# 07_MSM8916_GPIO.net
KiCad netlist of a schematic drawn in Altium Designer
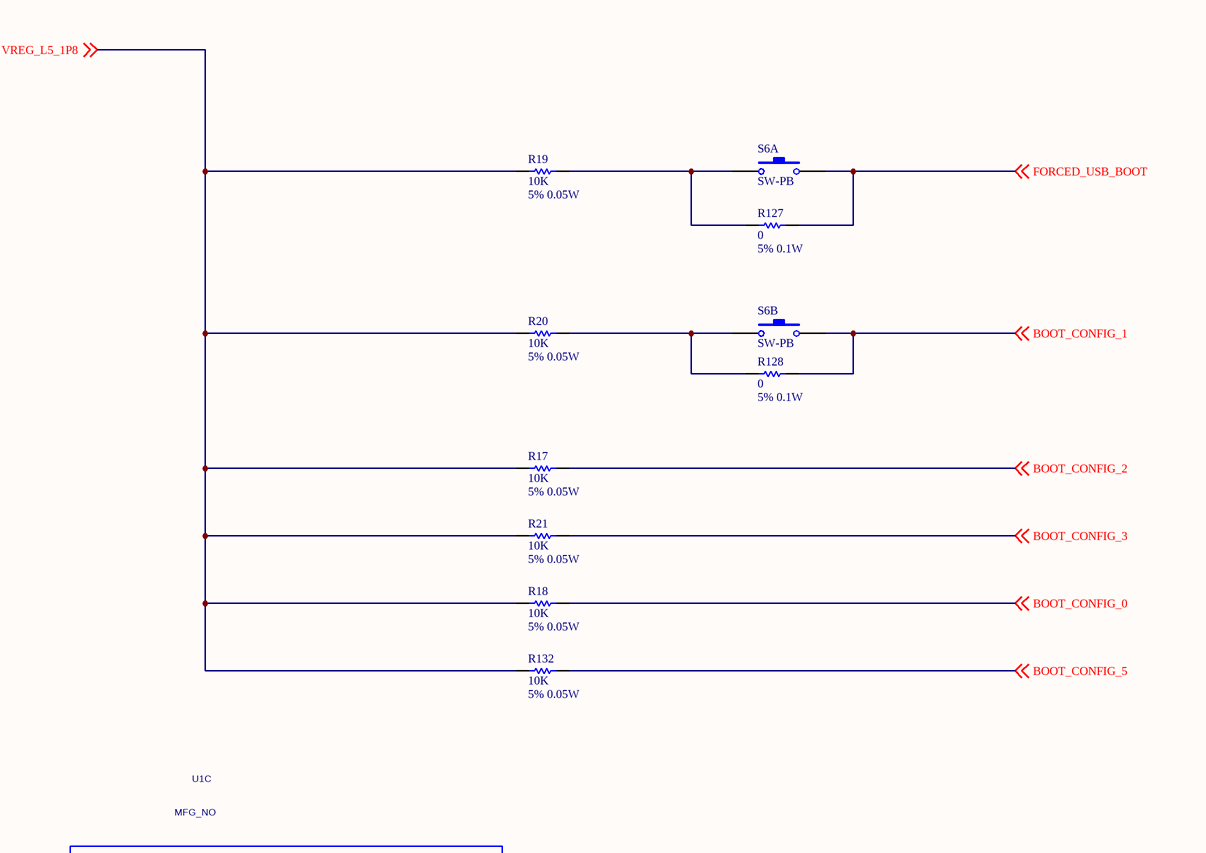
[diagram p0: 07_MSM8916_GPIO.SchDoc, top left]
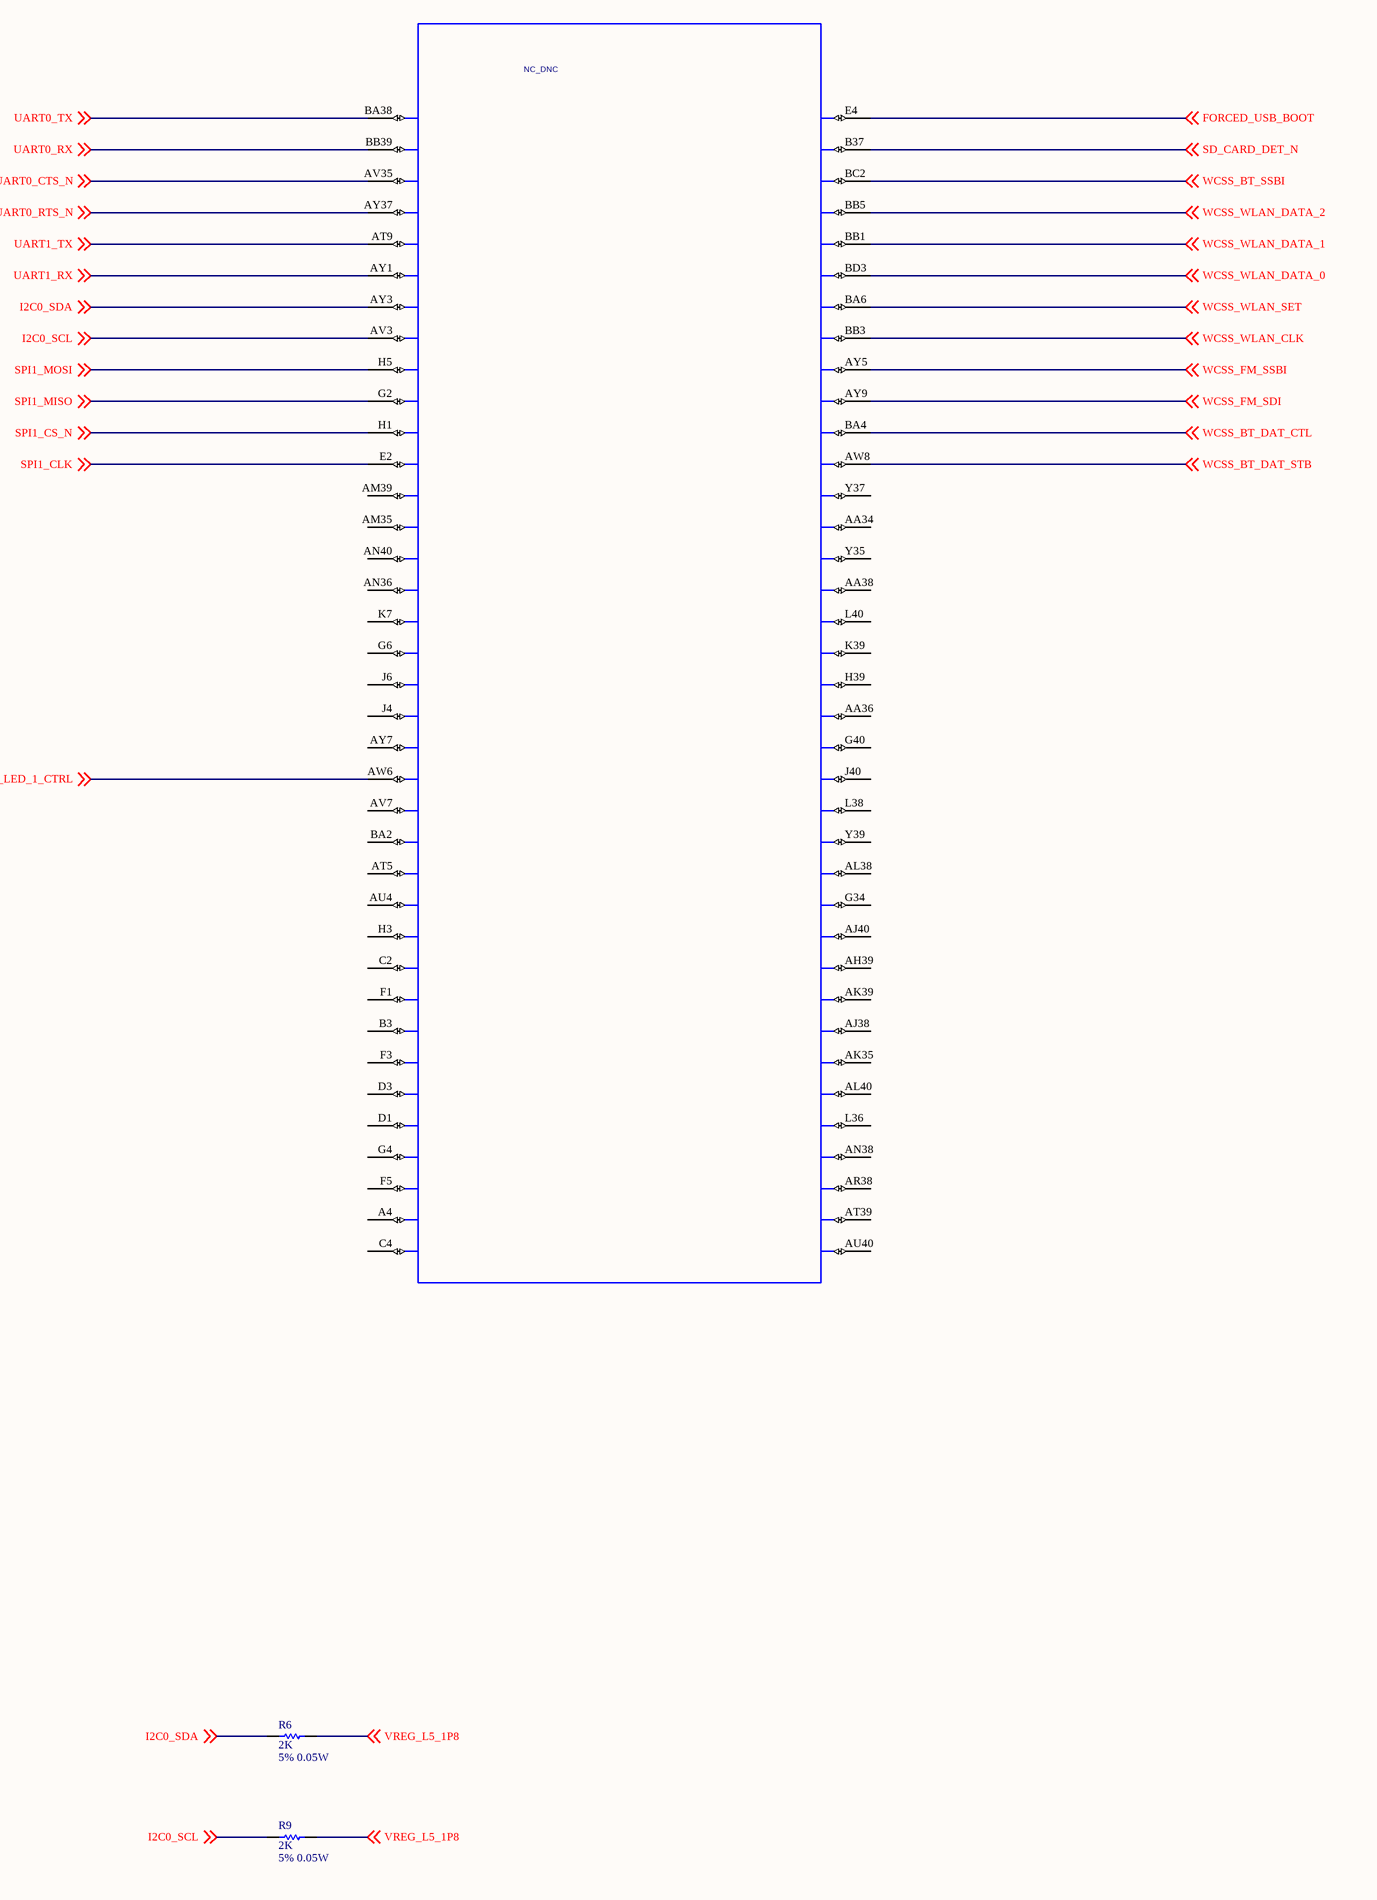
[diagram p1: 07_MSM8916_GPIO.SchDoc, bottom left]
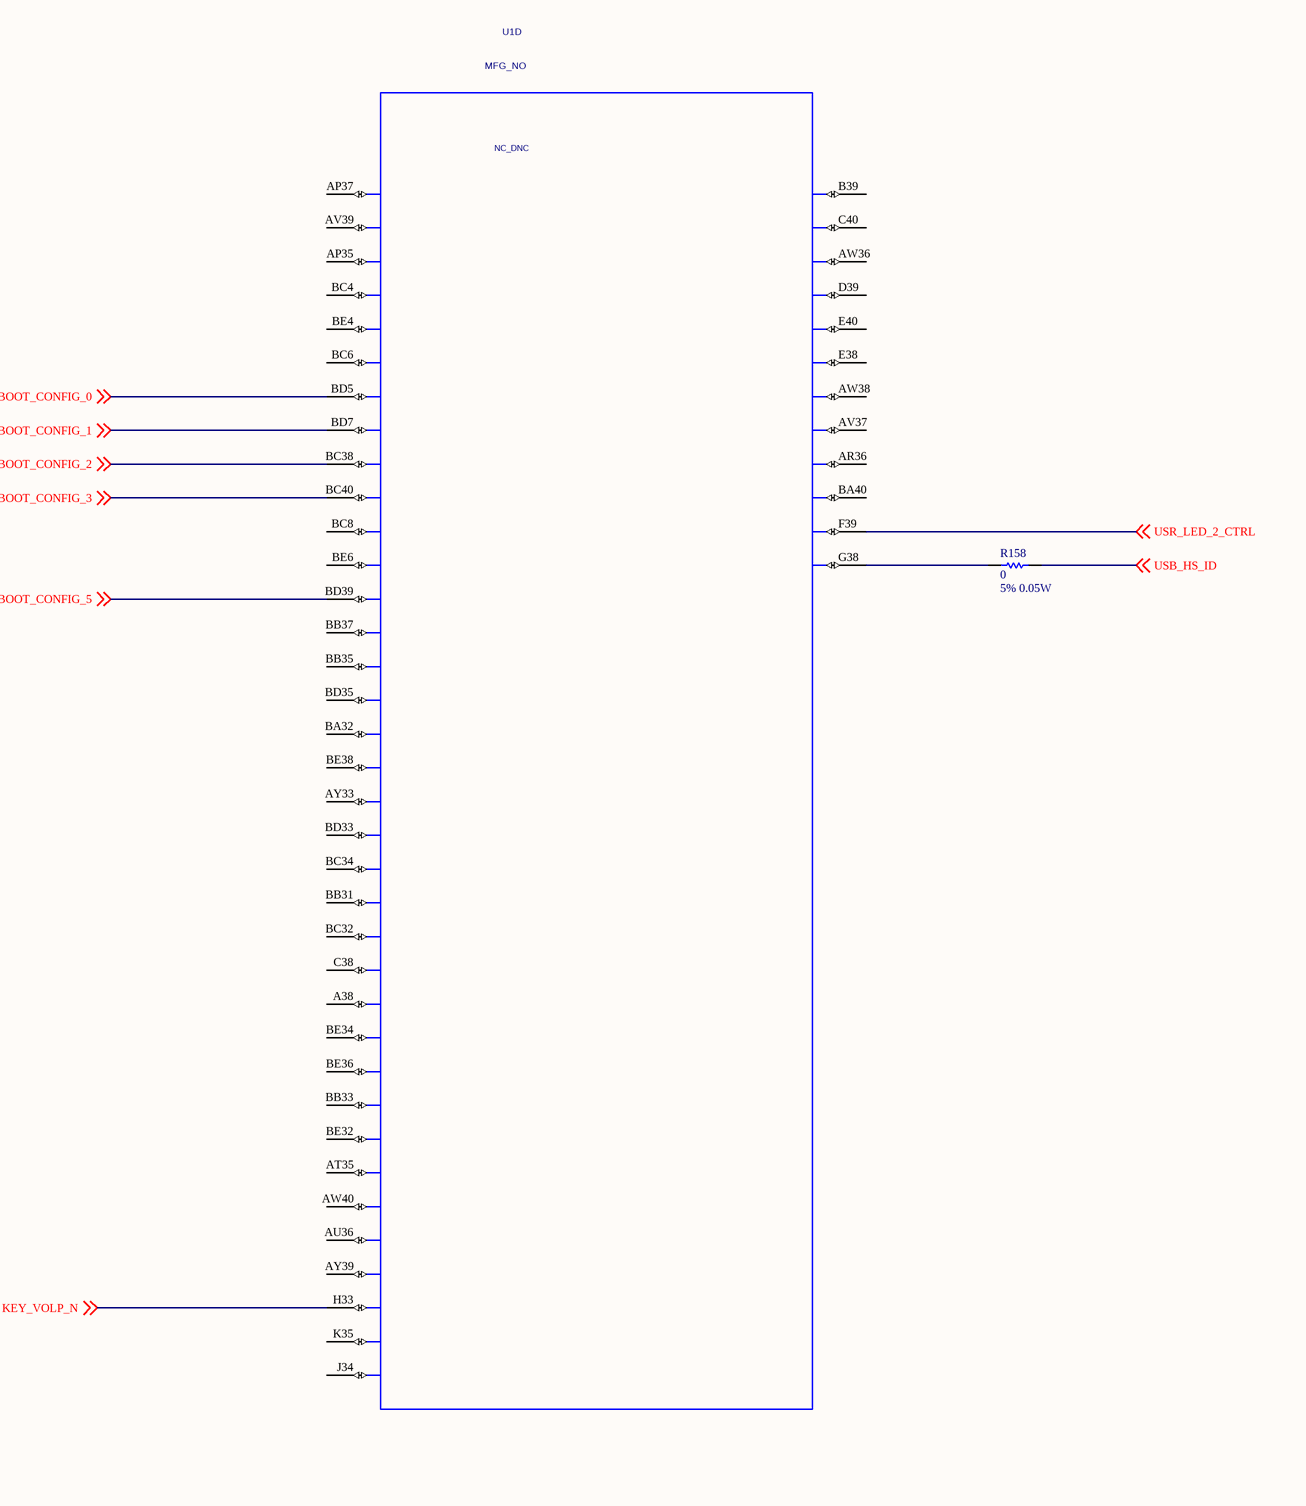
[diagram p2: 07_MSM8916_GPIO.SchDoc, bottom right]

(export (version "E")
  (design (tool "Eeschema 10.0.6"))
  (components
    (comp (ref "R6")
      (value "2K")
      (footprint "r0402")
      (description "Resistor")
      (fields (field (name "ALTIUM_VALUE") "5% 0.05W") (field (name "PUBLISHER") "Altium Limited"))
      (libsource (lib "Miscellaneous Devices") (part "Res1"))
    )
    (comp (ref "R9")
      (value "2K")
      (footprint "r0402")
      (description "Resistor")
      (fields (field (name "ALTIUM_VALUE") "5% 0.05W") (field (name "PUBLISHER") "Altium Limited"))
      (libsource (lib "Miscellaneous Devices") (part "Res1"))
    )
    (comp (ref "R17")
      (value "10K")
      (footprint "r0402")
      (description "Resistor")
      (fields (field (name "ALTIUM_VALUE") "5% 0.05W") (field (name "PUBLISHER") "Altium Limited"))
      (libsource (lib "Miscellaneous Devices") (part "Res1"))
    )
    (comp (ref "R18")
      (value "10K")
      (footprint "r0402")
      (description "Resistor")
      (fields (field (name "ALTIUM_VALUE") "5% 0.05W") (field (name "PUBLISHER") "Altium Limited"))
      (libsource (lib "Miscellaneous Devices") (part "Res1"))
    )
    (comp (ref "R19")
      (value "10K")
      (footprint "r0402")
      (description "Resistor")
      (fields (field (name "ALTIUM_VALUE") "5% 0.05W") (field (name "PUBLISHER") "Altium Limited"))
      (libsource (lib "Miscellaneous Devices") (part "Res1"))
    )
    (comp (ref "R20")
      (value "10K")
      (footprint "r0402")
      (description "Resistor")
      (fields (field (name "ALTIUM_VALUE") "5% 0.05W") (field (name "PUBLISHER") "Altium Limited"))
      (libsource (lib "Miscellaneous Devices") (part "Res1"))
    )
    (comp (ref "R21")
      (value "10K")
      (footprint "r0402")
      (description "Resistor")
      (fields (field (name "ALTIUM_VALUE") "5% 0.05W") (field (name "PUBLISHER") "Altium Limited"))
      (libsource (lib "Miscellaneous Devices") (part "Res1"))
    )
    (comp (ref "R127")
      (value "0")
      (footprint "r0402")
      (description "Resistor")
      (fields (field (name "ALTIUM_VALUE") "5% 0.1W") (field (name "PUBLISHER") "Altium Limited"))
      (libsource (lib "Miscellaneous Devices") (part "Res1"))
    )
    (comp (ref "R128")
      (value "0")
      (footprint "r0402")
      (description "Resistor")
      (fields (field (name "ALTIUM_VALUE") "5% 0.1W") (field (name "PUBLISHER") "Altium Limited"))
      (libsource (lib "Miscellaneous Devices") (part "Res1"))
    )
    (comp (ref "R132")
      (value "10K")
      (footprint "r0402")
      (description "Resistor")
      (fields (field (name "ALTIUM_VALUE") "5% 0.05W") (field (name "PUBLISHER") "Altium Limited"))
      (libsource (lib "Miscellaneous Devices") (part "Res1"))
    )
    (comp (ref "R158")
      (value "0")
      (footprint "r0402")
      (description "Resistor")
      (fields (field (name "ALTIUM_VALUE") "5% 0.05W") (field (name "PUBLISHER") "Altium Limited"))
      (libsource (lib "Miscellaneous Devices") (part "Res1"))
    )
    (comp (ref "S6A")
      (value "SW-PB")
      (footprint "SPST-2")
      (description "Switch")
      (fields (field (name "PUBLISHER") "Altium Limited"))
      (libsource (lib "Miscellaneous Devices") (part "SW-PB"))
    )
    (comp (ref "S6B")
      (value "SW-PB")
      (footprint "SPST-2")
      (description "Switch")
      (fields (field (name "PUBLISHER") "Altium Limited"))
      (libsource (lib "Miscellaneous Devices") (part "SW-PB"))
    )
    (comp (ref "U1")
      (value "ASIC_MSM8936_760PIN")
      (footprint "MSM-8916-0-760NSP-TR-00-0")
      (fields
        (field (name "PART_NUMBER") "MCN_NO")
        (field (name "SYMNAME") "NC_DNC")
        (field (name "PART_ID") "MFG_NO")
      )
      (libsource (lib "MSM8916_DRAM_PMIC_REF_Library") (part "ASIC_MSM8936_760PIN"))
    )
  )
  (nets
    (net (code "1") (name "BOOT_CONFIG_0") (class "Default")
      (node (ref "R18") (pin "2") (pinfunction "2_2") (pintype "passive"))
      (node (ref "U1") (pin "BD5") (pinfunction "GPIO_80_BD5") (pintype "bidirectional"))
    )
    (net (code "2") (name "BOOT_CONFIG_1") (class "Default")
      (node (ref "R128") (pin "2") (pinfunction "2_2") (pintype "passive"))
      (node (ref "S6B") (pin "2") (pinfunction "2_2") (pintype "passive"))
      (node (ref "U1") (pin "BD7") (pinfunction "GPIO_81_BD7") (pintype "bidirectional"))
    )
    (net (code "3") (name "BOOT_CONFIG_2") (class "Default")
      (node (ref "R17") (pin "2") (pinfunction "2_2") (pintype "passive"))
      (node (ref "U1") (pin "BC38") (pinfunction "GPIO_82_BC38") (pintype "bidirectional"))
    )
    (net (code "4") (name "BOOT_CONFIG_3") (class "Default")
      (node (ref "R21") (pin "2") (pinfunction "2_2") (pintype "passive"))
      (node (ref "U1") (pin "BC40") (pinfunction "GPIO_83_BC40") (pintype "bidirectional"))
    )
    (net (code "5") (name "BOOT_CONFIG_5") (class "Default")
      (node (ref "R132") (pin "2") (pinfunction "2_2") (pintype "passive"))
      (node (ref "U1") (pin "BD39") (pinfunction "GPIO_86_BD39") (pintype "bidirectional"))
    )
    (net (code "6") (name "FORCED_USB_BOOT") (class "Default")
      (node (ref "R127") (pin "2") (pinfunction "2_2") (pintype "passive"))
      (node (ref "S6A") (pin "2") (pinfunction "2_2") (pintype "passive"))
      (node (ref "U1") (pin "E4") (pinfunction "GPIO_37_E4") (pintype "bidirectional"))
    )
    (net (code "7") (name "I2C0_SCL") (class "Default")
      (node (ref "R9") (pin "2") (pinfunction "2_2") (pintype "passive"))
      (node (ref "U1") (pin "AV3") (pinfunction "GPIO_7_AV3") (pintype "bidirectional"))
    )
    (net (code "8") (name "I2C0_SDA") (class "Default")
      (node (ref "R6") (pin "2") (pinfunction "2_2") (pintype "passive"))
      (node (ref "U1") (pin "AY3") (pinfunction "GPIO_6_AY3") (pintype "bidirectional"))
    )
    (net (code "9") (name "KEY_VOLP_N") (class "Default")
      (node (ref "U1") (pin "H33") (pinfunction "GPIO_107_H33") (pintype "bidirectional"))
    )
    (net (code "10") (name "Net-(R127-Pad1)") (class "Default")
      (node (ref "R127") (pin "1") (pinfunction "1_1") (pintype "passive"))
      (node (ref "R19") (pin "2") (pinfunction "2_2") (pintype "passive"))
      (node (ref "S6A") (pin "1") (pinfunction "1_1") (pintype "passive"))
    )
    (net (code "11") (name "Net-(R128-Pad1)") (class "Default")
      (node (ref "R128") (pin "1") (pinfunction "1_1") (pintype "passive"))
      (node (ref "R20") (pin "2") (pinfunction "2_2") (pintype "passive"))
      (node (ref "S6B") (pin "1") (pinfunction "1_1") (pintype "passive"))
    )
    (net (code "12") (name "Net-(U1D-GPIO_121)") (class "Default")
      (node (ref "R158") (pin "1") (pinfunction "1_1") (pintype "passive"))
      (node (ref "U1") (pin "G38") (pinfunction "GPIO_121_G38") (pintype "bidirectional"))
    )
    (net (code "13") (name "SD_CARD_DET_N") (class "Default")
      (node (ref "U1") (pin "B37") (pinfunction "GPIO_38_B37") (pintype "bidirectional"))
    )
    (net (code "14") (name "SPI1_CLK") (class "Default")
      (node (ref "U1") (pin "E2") (pinfunction "GPIO_11_E2") (pintype "bidirectional"))
    )
    (net (code "15") (name "SPI1_CS_N") (class "Default")
      (node (ref "U1") (pin "H1") (pinfunction "GPIO_10_H1") (pintype "bidirectional"))
    )
    (net (code "16") (name "SPI1_MISO") (class "Default")
      (node (ref "U1") (pin "G2") (pinfunction "GPIO_9_G2") (pintype "bidirectional"))
    )
    (net (code "17") (name "SPI1_MOSI") (class "Default")
      (node (ref "U1") (pin "H5") (pinfunction "GPIO_8_H5") (pintype "bidirectional"))
    )
    (net (code "18") (name "UART0_CTS_N") (class "Default")
      (node (ref "U1") (pin "AV35") (pinfunction "GPIO_2_AV35") (pintype "bidirectional"))
    )
    (net (code "19") (name "UART0_RTS_N") (class "Default")
      (node (ref "U1") (pin "AY37") (pinfunction "GPIO_3_AY37") (pintype "bidirectional"))
    )
    (net (code "20") (name "UART0_RX") (class "Default")
      (node (ref "U1") (pin "BB39") (pinfunction "GPIO_1_BB39") (pintype "bidirectional"))
    )
    (net (code "21") (name "UART0_TX") (class "Default")
      (node (ref "U1") (pin "BA38") (pinfunction "GPIO_0_BA38") (pintype "bidirectional"))
    )
    (net (code "22") (name "UART1_RX") (class "Default")
      (node (ref "U1") (pin "AY1") (pinfunction "GPIO_5_AY1") (pintype "bidirectional"))
    )
    (net (code "23") (name "UART1_TX") (class "Default")
      (node (ref "U1") (pin "AT9") (pinfunction "GPIO_4_AT9") (pintype "bidirectional"))
    )
    (net (code "24") (name "USB_HS_ID") (class "Default")
      (node (ref "R158") (pin "2") (pinfunction "2_2") (pintype "passive"))
    )
    (net (code "25") (name "USR_LED_1_CTRL") (class "Default")
      (node (ref "U1") (pin "AW6") (pinfunction "GPIO_21_AW6") (pintype "bidirectional"))
    )
    (net (code "26") (name "USR_LED_2_CTRL") (class "Default")
      (node (ref "U1") (pin "F39") (pinfunction "GPIO_120_F39") (pintype "bidirectional"))
    )
    (net (code "27") (name "VREG_L5_1P8") (class "Default")
      (node (ref "R132") (pin "1") (pinfunction "1_1") (pintype "passive"))
      (node (ref "R17") (pin "1") (pinfunction "1_1") (pintype "passive"))
      (node (ref "R18") (pin "1") (pinfunction "1_1") (pintype "passive"))
      (node (ref "R19") (pin "1") (pinfunction "1_1") (pintype "passive"))
      (node (ref "R20") (pin "1") (pinfunction "1_1") (pintype "passive"))
      (node (ref "R21") (pin "1") (pinfunction "1_1") (pintype "passive"))
      (node (ref "R6") (pin "1") (pinfunction "1_1") (pintype "passive"))
      (node (ref "R9") (pin "1") (pinfunction "1_1") (pintype "passive"))
    )
    (net (code "28") (name "WCSS_BT_DAT_CTL") (class "Default")
      (node (ref "U1") (pin "BA4") (pinfunction "GPIO_47_BA4") (pintype "bidirectional"))
    )
    (net (code "29") (name "WCSS_BT_DAT_STB") (class "Default")
      (node (ref "U1") (pin "AW8") (pinfunction "GPIO_48_AW8") (pintype "bidirectional"))
    )
    (net (code "30") (name "WCSS_BT_SSBI") (class "Default")
      (node (ref "U1") (pin "BC2") (pinfunction "GPIO_39_BC2") (pintype "bidirectional"))
    )
    (net (code "31") (name "WCSS_FM_SDI") (class "Default")
      (node (ref "U1") (pin "AY9") (pinfunction "GPIO_46_AY9") (pintype "bidirectional"))
    )
    (net (code "32") (name "WCSS_FM_SSBI") (class "Default")
      (node (ref "U1") (pin "AY5") (pinfunction "GPIO_45_AY5") (pintype "bidirectional"))
    )
    (net (code "33") (name "WCSS_WLAN_CLK") (class "Default")
      (node (ref "U1") (pin "BB3") (pinfunction "GPIO_44_BB3") (pintype "bidirectional"))
    )
    (net (code "34") (name "WCSS_WLAN_DATA_0") (class "Default")
      (node (ref "U1") (pin "BD3") (pinfunction "GPIO_42_BD3") (pintype "bidirectional"))
    )
    (net (code "35") (name "WCSS_WLAN_DATA_1") (class "Default")
      (node (ref "U1") (pin "BB1") (pinfunction "GPIO_41_BB1") (pintype "bidirectional"))
    )
    (net (code "36") (name "WCSS_WLAN_DATA_2") (class "Default")
      (node (ref "U1") (pin "BB5") (pinfunction "GPIO_40_BB5") (pintype "bidirectional"))
    )
    (net (code "37") (name "WCSS_WLAN_SET") (class "Default")
      (node (ref "U1") (pin "BA6") (pinfunction "GPIO_43_BA6") (pintype "bidirectional"))
    )
    (net (code "38") (name "unconnected-(U1C-GPIO_12-PadAM39)") (class "Default")
      (node (ref "U1") (pin "AM39") (pinfunction "GPIO_12_AM39") (pintype "bidirectional"))
    )
    (net (code "39") (name "unconnected-(U1C-GPIO_13-PadAM35)") (class "Default")
      (node (ref "U1") (pin "AM35") (pinfunction "GPIO_13_AM35") (pintype "bidirectional"))
    )
    (net (code "40") (name "unconnected-(U1C-GPIO_14-PadAN40)") (class "Default")
      (node (ref "U1") (pin "AN40") (pinfunction "GPIO_14_AN40") (pintype "bidirectional"))
    )
    (net (code "41") (name "unconnected-(U1C-GPIO_15-PadAN36)") (class "Default")
      (node (ref "U1") (pin "AN36") (pinfunction "GPIO_15_AN36") (pintype "bidirectional"))
    )
    (net (code "42") (name "unconnected-(U1C-GPIO_16-PadK7)") (class "Default")
      (node (ref "U1") (pin "K7") (pinfunction "GPIO_16_K7") (pintype "bidirectional"))
    )
    (net (code "43") (name "unconnected-(U1C-GPIO_17-PadG6)") (class "Default")
      (node (ref "U1") (pin "G6") (pinfunction "GPIO_17_G6") (pintype "bidirectional"))
    )
    (net (code "44") (name "unconnected-(U1C-GPIO_18-PadJ6)") (class "Default")
      (node (ref "U1") (pin "J6") (pinfunction "GPIO_18_J6") (pintype "bidirectional"))
    )
    (net (code "45") (name "unconnected-(U1C-GPIO_19-PadJ4)") (class "Default")
      (node (ref "U1") (pin "J4") (pinfunction "GPIO_19_J4") (pintype "bidirectional"))
    )
    (net (code "46") (name "unconnected-(U1C-GPIO_20-PadAY7)") (class "Default")
      (node (ref "U1") (pin "AY7") (pinfunction "GPIO_20_AY7") (pintype "bidirectional"))
    )
    (net (code "47") (name "unconnected-(U1C-GPIO_22-PadAV7)") (class "Default")
      (node (ref "U1") (pin "AV7") (pinfunction "GPIO_22_AV7") (pintype "bidirectional"))
    )
    (net (code "48") (name "unconnected-(U1C-GPIO_23-PadBA2)") (class "Default")
      (node (ref "U1") (pin "BA2") (pinfunction "GPIO_23_BA2") (pintype "bidirectional"))
    )
    (net (code "49") (name "unconnected-(U1C-GPIO_24-PadAT5)") (class "Default")
      (node (ref "U1") (pin "AT5") (pinfunction "GPIO_24_AT5") (pintype "bidirectional"))
    )
    (net (code "50") (name "unconnected-(U1C-GPIO_25-PadAU4)") (class "Default")
      (node (ref "U1") (pin "AU4") (pinfunction "GPIO_25_AU4") (pintype "bidirectional"))
    )
    (net (code "51") (name "unconnected-(U1C-GPIO_26-PadH3)") (class "Default")
      (node (ref "U1") (pin "H3") (pinfunction "GPIO_26_H3") (pintype "bidirectional"))
    )
    (net (code "52") (name "unconnected-(U1C-GPIO_27-PadC2)") (class "Default")
      (node (ref "U1") (pin "C2") (pinfunction "GPIO_27_C2") (pintype "bidirectional"))
    )
    (net (code "53") (name "unconnected-(U1C-GPIO_28-PadF1)") (class "Default")
      (node (ref "U1") (pin "F1") (pinfunction "GPIO_28_F1") (pintype "bidirectional"))
    )
    (net (code "54") (name "unconnected-(U1C-GPIO_29-PadB3)") (class "Default")
      (node (ref "U1") (pin "B3") (pinfunction "GPIO_29_B3") (pintype "bidirectional"))
    )
    (net (code "55") (name "unconnected-(U1C-GPIO_30-PadF3)") (class "Default")
      (node (ref "U1") (pin "F3") (pinfunction "GPIO_30_F3") (pintype "bidirectional"))
    )
    (net (code "56") (name "unconnected-(U1C-GPIO_31-PadD3)") (class "Default")
      (node (ref "U1") (pin "D3") (pinfunction "GPIO_31_D3") (pintype "bidirectional"))
    )
    (net (code "57") (name "unconnected-(U1C-GPIO_32-PadD1)") (class "Default")
      (node (ref "U1") (pin "D1") (pinfunction "GPIO_32_D1") (pintype "bidirectional"))
    )
    (net (code "58") (name "unconnected-(U1C-GPIO_33-PadG4)") (class "Default")
      (node (ref "U1") (pin "G4") (pinfunction "GPIO_33_G4") (pintype "bidirectional"))
    )
    (net (code "59") (name "unconnected-(U1C-GPIO_34-PadF5)") (class "Default")
      (node (ref "U1") (pin "F5") (pinfunction "GPIO_34_F5") (pintype "bidirectional"))
    )
    (net (code "60") (name "unconnected-(U1C-GPIO_35-PadA4)") (class "Default")
      (node (ref "U1") (pin "A4") (pinfunction "GPIO_35_A4") (pintype "bidirectional"))
    )
    (net (code "61") (name "unconnected-(U1C-GPIO_36-PadC4)") (class "Default")
      (node (ref "U1") (pin "C4") (pinfunction "GPIO_36_C4") (pintype "bidirectional"))
    )
    (net (code "62") (name "unconnected-(U1C-GPIO_49-PadY37)") (class "Default")
      (node (ref "U1") (pin "Y37") (pinfunction "GPIO_49_Y37") (pintype "bidirectional"))
    )
    (net (code "63") (name "unconnected-(U1C-GPIO_50-PadAA34)") (class "Default")
      (node (ref "U1") (pin "AA34") (pinfunction "GPIO_50_AA34") (pintype "bidirectional"))
    )
    (net (code "64") (name "unconnected-(U1C-GPIO_51-PadY35)") (class "Default")
      (node (ref "U1") (pin "Y35") (pinfunction "GPIO_51_Y35") (pintype "bidirectional"))
    )
    (net (code "65") (name "unconnected-(U1C-GPIO_52-PadAA38)") (class "Default")
      (node (ref "U1") (pin "AA38") (pinfunction "GPIO_52_AA38") (pintype "bidirectional"))
    )
    (net (code "66") (name "unconnected-(U1C-GPIO_53-PadL40)") (class "Default")
      (node (ref "U1") (pin "L40") (pinfunction "GPIO_53_L40") (pintype "bidirectional"))
    )
    (net (code "67") (name "unconnected-(U1C-GPIO_54-PadK39)") (class "Default")
      (node (ref "U1") (pin "K39") (pinfunction "GPIO_54_K39") (pintype "bidirectional"))
    )
    (net (code "68") (name "unconnected-(U1C-GPIO_55-PadH39)") (class "Default")
      (node (ref "U1") (pin "H39") (pinfunction "GPIO_55_H39") (pintype "bidirectional"))
    )
    (net (code "69") (name "unconnected-(U1C-GPIO_56-PadAA36)") (class "Default")
      (node (ref "U1") (pin "AA36") (pinfunction "GPIO_56_AA36") (pintype "bidirectional"))
    )
    (net (code "70") (name "unconnected-(U1C-GPIO_57-PadG40)") (class "Default")
      (node (ref "U1") (pin "G40") (pinfunction "GPIO_57_G40") (pintype "bidirectional"))
    )
    (net (code "71") (name "unconnected-(U1C-GPIO_58-PadJ40)") (class "Default")
      (node (ref "U1") (pin "J40") (pinfunction "GPIO_58_J40") (pintype "bidirectional"))
    )
    (net (code "72") (name "unconnected-(U1C-GPIO_59-PadL38)") (class "Default")
      (node (ref "U1") (pin "L38") (pinfunction "GPIO_59_L38") (pintype "bidirectional"))
    )
    (net (code "73") (name "unconnected-(U1C-GPIO_60-PadY39)") (class "Default")
      (node (ref "U1") (pin "Y39") (pinfunction "GPIO_60_Y39") (pintype "bidirectional"))
    )
    (net (code "74") (name "unconnected-(U1C-GPIO_61-PadAL38)") (class "Default")
      (node (ref "U1") (pin "AL38") (pinfunction "GPIO_61_AL38") (pintype "bidirectional"))
    )
    (net (code "75") (name "unconnected-(U1C-GPIO_62-PadG34)") (class "Default")
      (node (ref "U1") (pin "G34") (pinfunction "GPIO_62_G34") (pintype "bidirectional"))
    )
    (net (code "76") (name "unconnected-(U1C-GPIO_63-PadAJ40)") (class "Default")
      (node (ref "U1") (pin "AJ40") (pinfunction "GPIO_63_AJ40") (pintype "bidirectional"))
    )
    (net (code "77") (name "unconnected-(U1C-GPIO_64-PadAH39)") (class "Default")
      (node (ref "U1") (pin "AH39") (pinfunction "GPIO_64_AH39") (pintype "bidirectional"))
    )
    (net (code "78") (name "unconnected-(U1C-GPIO_65-PadAK39)") (class "Default")
      (node (ref "U1") (pin "AK39") (pinfunction "GPIO_65_AK39") (pintype "bidirectional"))
    )
    (net (code "79") (name "unconnected-(U1C-GPIO_66-PadAJ38)") (class "Default")
      (node (ref "U1") (pin "AJ38") (pinfunction "GPIO_66_AJ38") (pintype "bidirectional"))
    )
    (net (code "80") (name "unconnected-(U1C-GPIO_67-PadAK35)") (class "Default")
      (node (ref "U1") (pin "AK35") (pinfunction "GPIO_67_AK35") (pintype "bidirectional"))
    )
    (net (code "81") (name "unconnected-(U1C-GPIO_68-PadAL40)") (class "Default")
      (node (ref "U1") (pin "AL40") (pinfunction "GPIO_68_AL40") (pintype "bidirectional"))
    )
    (net (code "82") (name "unconnected-(U1C-GPIO_69-PadL36)") (class "Default")
      (node (ref "U1") (pin "L36") (pinfunction "GPIO_69_L36") (pintype "bidirectional"))
    )
    (net (code "83") (name "unconnected-(U1C-GPIO_70-PadAN38)") (class "Default")
      (node (ref "U1") (pin "AN38") (pinfunction "GPIO_70_AN38") (pintype "bidirectional"))
    )
    (net (code "84") (name "unconnected-(U1C-GPIO_71-PadAR38)") (class "Default")
      (node (ref "U1") (pin "AR38") (pinfunction "GPIO_71_AR38") (pintype "bidirectional"))
    )
    (net (code "85") (name "unconnected-(U1C-GPIO_72-PadAT39)") (class "Default")
      (node (ref "U1") (pin "AT39") (pinfunction "GPIO_72_AT39") (pintype "bidirectional"))
    )
    (net (code "86") (name "unconnected-(U1C-GPIO_73-PadAU40)") (class "Default")
      (node (ref "U1") (pin "AU40") (pinfunction "GPIO_73_AU40") (pintype "bidirectional"))
    )
    (net (code "87") (name "unconnected-(U1D-GPIO_74-PadAP37)") (class "Default")
      (node (ref "U1") (pin "AP37") (pinfunction "GPIO_74_AP37") (pintype "bidirectional"))
    )
    (net (code "88") (name "unconnected-(U1D-GPIO_75-PadAV39)") (class "Default")
      (node (ref "U1") (pin "AV39") (pinfunction "GPIO_75_AV39") (pintype "bidirectional"))
    )
    (net (code "89") (name "unconnected-(U1D-GPIO_76-PadAP35)") (class "Default")
      (node (ref "U1") (pin "AP35") (pinfunction "GPIO_76_AP35") (pintype "bidirectional"))
    )
    (net (code "90") (name "unconnected-(U1D-GPIO_77-PadBC4)") (class "Default")
      (node (ref "U1") (pin "BC4") (pinfunction "GPIO_77_BC4") (pintype "bidirectional"))
    )
    (net (code "91") (name "unconnected-(U1D-GPIO_78-PadBE4)") (class "Default")
      (node (ref "U1") (pin "BE4") (pinfunction "GPIO_78_BE4") (pintype "bidirectional"))
    )
    (net (code "92") (name "unconnected-(U1D-GPIO_79-PadBC6)") (class "Default")
      (node (ref "U1") (pin "BC6") (pinfunction "GPIO_79_BC6") (pintype "bidirectional"))
    )
    (net (code "93") (name "unconnected-(U1D-GPIO_84-PadBC8)") (class "Default")
      (node (ref "U1") (pin "BC8") (pinfunction "GPIO_84_BC8") (pintype "bidirectional"))
    )
    (net (code "94") (name "unconnected-(U1D-GPIO_85-PadBE6)") (class "Default")
      (node (ref "U1") (pin "BE6") (pinfunction "GPIO_85_BE6") (pintype "bidirectional"))
    )
    (net (code "95") (name "unconnected-(U1D-GPIO_87-PadBB37)") (class "Default")
      (node (ref "U1") (pin "BB37") (pinfunction "GPIO_87_BB37") (pintype "bidirectional"))
    )
    (net (code "96") (name "unconnected-(U1D-GPIO_88-PadBB35)") (class "Default")
      (node (ref "U1") (pin "BB35") (pinfunction "GPIO_88_BB35") (pintype "bidirectional"))
    )
    (net (code "97") (name "unconnected-(U1D-GPIO_89-PadBD35)") (class "Default")
      (node (ref "U1") (pin "BD35") (pinfunction "GPIO_89_BD35") (pintype "bidirectional"))
    )
    (net (code "98") (name "unconnected-(U1D-GPIO_90-PadBA32)") (class "Default")
      (node (ref "U1") (pin "BA32") (pinfunction "GPIO_90_BA32") (pintype "bidirectional"))
    )
    (net (code "99") (name "unconnected-(U1D-GPIO_91-PadBE38)") (class "Default")
      (node (ref "U1") (pin "BE38") (pinfunction "GPIO_91_BE38") (pintype "bidirectional"))
    )
    (net (code "100") (name "unconnected-(U1D-GPIO_92-PadAY33)") (class "Default")
      (node (ref "U1") (pin "AY33") (pinfunction "GPIO_92_AY33") (pintype "bidirectional"))
    )
    (net (code "101") (name "unconnected-(U1D-GPIO_93-PadBD33)") (class "Default")
      (node (ref "U1") (pin "BD33") (pinfunction "GPIO_93_BD33") (pintype "bidirectional"))
    )
    (net (code "102") (name "unconnected-(U1D-GPIO_94-PadBC34)") (class "Default")
      (node (ref "U1") (pin "BC34") (pinfunction "GPIO_94_BC34") (pintype "bidirectional"))
    )
    (net (code "103") (name "unconnected-(U1D-GPIO_95-PadBB31)") (class "Default")
      (node (ref "U1") (pin "BB31") (pinfunction "GPIO_95_BB31") (pintype "bidirectional"))
    )
    (net (code "104") (name "unconnected-(U1D-GPIO_96-PadBC32)") (class "Default")
      (node (ref "U1") (pin "BC32") (pinfunction "GPIO_96_BC32") (pintype "bidirectional"))
    )
    (net (code "105") (name "unconnected-(U1D-GPIO_97-PadC38)") (class "Default")
      (node (ref "U1") (pin "C38") (pinfunction "GPIO_97_C38") (pintype "bidirectional"))
    )
    (net (code "106") (name "unconnected-(U1D-GPIO_98-PadA38)") (class "Default")
      (node (ref "U1") (pin "A38") (pinfunction "GPIO_98_A38") (pintype "bidirectional"))
    )
    (net (code "107") (name "unconnected-(U1D-GPIO_99-PadBE34)") (class "Default")
      (node (ref "U1") (pin "BE34") (pinfunction "GPIO_99_BE34") (pintype "bidirectional"))
    )
    (net (code "108") (name "unconnected-(U1D-GPIO_100-PadBE36)") (class "Default")
      (node (ref "U1") (pin "BE36") (pinfunction "GPIO_100_BE36") (pintype "bidirectional"))
    )
    (net (code "109") (name "unconnected-(U1D-GPIO_101-PadBB33)") (class "Default")
      (node (ref "U1") (pin "BB33") (pinfunction "GPIO_101_BB33") (pintype "bidirectional"))
    )
    (net (code "110") (name "unconnected-(U1D-GPIO_102-PadBE32)") (class "Default")
      (node (ref "U1") (pin "BE32") (pinfunction "GPIO_102_BE32") (pintype "bidirectional"))
    )
    (net (code "111") (name "unconnected-(U1D-GPIO_103-PadAT35)") (class "Default")
      (node (ref "U1") (pin "AT35") (pinfunction "GPIO_103_AT35") (pintype "bidirectional"))
    )
    (net (code "112") (name "unconnected-(U1D-GPIO_104-PadAW40)") (class "Default")
      (node (ref "U1") (pin "AW40") (pinfunction "GPIO_104_AW40") (pintype "bidirectional"))
    )
    (net (code "113") (name "unconnected-(U1D-GPIO_105-PadAU36)") (class "Default")
      (node (ref "U1") (pin "AU36") (pinfunction "GPIO_105_AU36") (pintype "bidirectional"))
    )
    (net (code "114") (name "unconnected-(U1D-GPIO_106-PadAY39)") (class "Default")
      (node (ref "U1") (pin "AY39") (pinfunction "GPIO_106_AY39") (pintype "bidirectional"))
    )
    (net (code "115") (name "unconnected-(U1D-GPIO_108-PadK35)") (class "Default")
      (node (ref "U1") (pin "K35") (pinfunction "GPIO_108_K35") (pintype "bidirectional"))
    )
    (net (code "116") (name "unconnected-(U1D-GPIO_109-PadJ34)") (class "Default")
      (node (ref "U1") (pin "J34") (pinfunction "GPIO_109_J34") (pintype "bidirectional"))
    )
    (net (code "117") (name "unconnected-(U1D-GPIO_110-PadB39)") (class "Default")
      (node (ref "U1") (pin "B39") (pinfunction "GPIO_110_B39") (pintype "bidirectional"))
    )
    (net (code "118") (name "unconnected-(U1D-GPIO_111-PadC40)") (class "Default")
      (node (ref "U1") (pin "C40") (pinfunction "GPIO_111_C40") (pintype "bidirectional"))
    )
    (net (code "119") (name "unconnected-(U1D-GPIO_112-PadAW36)") (class "Default")
      (node (ref "U1") (pin "AW36") (pinfunction "GPIO_112_AW36") (pintype "bidirectional"))
    )
    (net (code "120") (name "unconnected-(U1D-GPIO_113-PadD39)") (class "Default")
      (node (ref "U1") (pin "D39") (pinfunction "GPIO_113_D39") (pintype "bidirectional"))
    )
    (net (code "121") (name "unconnected-(U1D-GPIO_114-PadE40)") (class "Default")
      (node (ref "U1") (pin "E40") (pinfunction "GPIO_114_E40") (pintype "bidirectional"))
    )
    (net (code "122") (name "unconnected-(U1D-GPIO_115-PadE38)") (class "Default")
      (node (ref "U1") (pin "E38") (pinfunction "GPIO_115_E38") (pintype "bidirectional"))
    )
    (net (code "123") (name "unconnected-(U1D-GPIO_116-PadAW38)") (class "Default")
      (node (ref "U1") (pin "AW38") (pinfunction "GPIO_116_AW38") (pintype "bidirectional"))
    )
    (net (code "124") (name "unconnected-(U1D-GPIO_117-PadAV37)") (class "Default")
      (node (ref "U1") (pin "AV37") (pinfunction "GPIO_117_AV37") (pintype "bidirectional"))
    )
    (net (code "125") (name "unconnected-(U1D-GPIO_118-PadAR36)") (class "Default")
      (node (ref "U1") (pin "AR36") (pinfunction "GPIO_118_AR36") (pintype "bidirectional"))
    )
    (net (code "126") (name "unconnected-(U1D-GPIO_119-PadBA40)") (class "Default")
      (node (ref "U1") (pin "BA40") (pinfunction "GPIO_119_BA40") (pintype "bidirectional"))
    )
  )
)
